# 7_power_prot_mon.net
KiCad netlist of a schematic drawn in Altium Designer
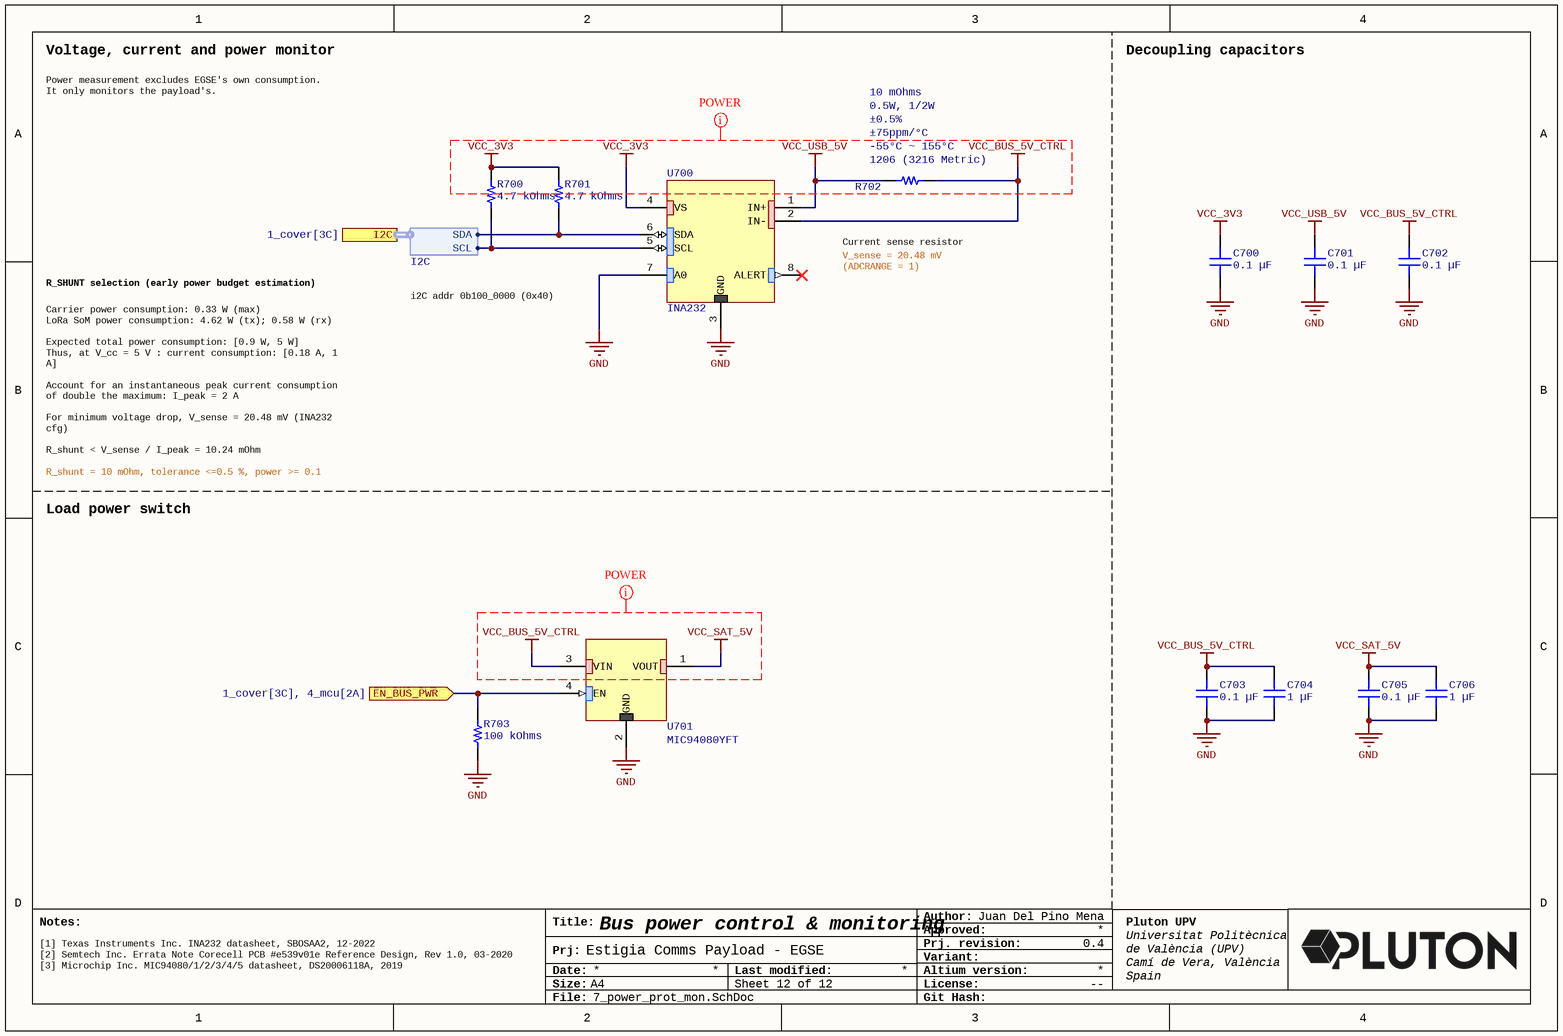
[diagram p0: 7_power_prot_mon.SchDoc]

(export (version "E")
  (design (tool "Eeschema 10.0.6"))
  (components
    (comp (ref "C700")
      (value "0.1 µF")
      (footprint "CAP 0402_1005")
      (description "CAP CER 0402 0.1UF 16V X7R 10%")
      (fields (field (name "PART NUMBER") "C0402C104K4RECAUTO") (field (name "MANUFACTURER") "KEMET"))
      (libsource (lib "Celestial Altium Library - altium_library") (part "Capacitor"))
    )
    (comp (ref "C701")
      (value "0.1 µF")
      (footprint "CAP 0402_1005")
      (description "CAP CER 0402 0.1UF 16V X7R 10%")
      (fields (field (name "PART NUMBER") "C0402C104K4RECAUTO") (field (name "MANUFACTURER") "KEMET"))
      (libsource (lib "Celestial Altium Library - altium_library") (part "Capacitor"))
    )
    (comp (ref "C702")
      (value "0.1 µF")
      (footprint "CAP 0402_1005")
      (description "CAP CER 0402 0.1UF 16V X7R 10%")
      (fields (field (name "PART NUMBER") "C0402C104K4RECAUTO") (field (name "MANUFACTURER") "KEMET"))
      (libsource (lib "Celestial Altium Library - altium_library") (part "Capacitor"))
    )
    (comp (ref "C703")
      (value "0.1 µF")
      (footprint "CAP 0402_1005")
      (description "CAP CER 0402 0.1UF 16V X7R 10%")
      (fields (field (name "PART NUMBER") "C0402C104K4RECAUTO") (field (name "MANUFACTURER") "KEMET"))
      (libsource (lib "Celestial Altium Library - altium_library") (part "Capacitor"))
    )
    (comp (ref "C704")
      (value "1 µF")
      (footprint "CAP 0402_1005")
      (description "CAP CER 1UF 10V X7S 0402")
      (fields
        (field (name "PART NUMBER") "GRT155C71A105KE13D")
        (field (name "MANUFACTURER") "Murata Electronics")
      )
      (libsource (lib "Celestial Altium Library - altium_library") (part "Capacitor"))
    )
    (comp (ref "C705")
      (value "0.1 µF")
      (footprint "CAP 0402_1005")
      (description "CAP CER 0402 0.1UF 16V X7R 10%")
      (fields (field (name "PART NUMBER") "C0402C104K4RECAUTO") (field (name "MANUFACTURER") "KEMET"))
      (libsource (lib "Celestial Altium Library - altium_library") (part "Capacitor"))
    )
    (comp (ref "C706")
      (value "1 µF")
      (footprint "CAP 0402_1005")
      (description "CAP CER 1UF 10V X7S 0402")
      (fields
        (field (name "PART NUMBER") "GRT155C71A105KE13D")
        (field (name "MANUFACTURER") "Murata Electronics")
      )
      (libsource (lib "Celestial Altium Library - altium_library") (part "Capacitor"))
    )
    (comp (ref "R700")
      (value "4.7 kOhms")
      (footprint "RES 0201_0603")
      (description "RES SMD 4.7K OHM 1% 1/20W 0201")
      (fields (field (name "PART NUMBER") "AC0201FR-074K7L") (field (name "MANUFACTURER") "Yageo"))
      (libsource (lib "Celestial Altium Library - altium_library") (part "Resistor"))
    )
    (comp (ref "R701")
      (value "4.7 kOhms")
      (footprint "RES 0201_0603")
      (description "RES SMD 4.7K OHM 1% 1/20W 0201")
      (fields (field (name "PART NUMBER") "AC0201FR-074K7L") (field (name "MANUFACTURER") "Yageo"))
      (libsource (lib "Celestial Altium Library - altium_library") (part "Resistor"))
    )
    (comp (ref "R702")
      (value "10 mOhms")
      (footprint "STACKPOLE CSR1206")
      (description "0.01 OHM 1206 0.5% 0.50W")
      (fields
        (field (name "PART NUMBER") "L4T12FR010DER")
        (field (name "PACKAGE / CASE") "1206 (3216 Metric)")
        (field (name "MANUFACTURER") "Ohmite")
        (field (name "OPERATING TEMPERATURE") "-55°C ~ 155°C")
        (field (name "POWER (WATTS)") "0.5W, 1/2W")
        (field (name "RESISTANCE") "10 mOhms")
        (field (name "TEMPERATURE COEFFICIENT") "±75ppm/°C")
        (field (name "TOLERANCE") "±0.5%")
      )
      (libsource (lib "Celestial Altium Library - altium_library") (part "Resistor"))
    )
    (comp (ref "R703")
      (value "100 kOhms")
      (footprint "RES 0201_0603")
      (description "RES 100K OHM 1% 1/20W 0201")
      (fields (field (name "PART NUMBER") "RC0201FR-13100KL") (field (name "MANUFACTURER") "Yageo"))
      (libsource (lib "Celestial Altium Library - altium_library") (part "Resistor"))
    )
    (comp (ref "U700")
      (value "INA232")
      (footprint "ics:SOp-23-8")
      (description "48-V, 16-Bit, Current, Voltage, and Power Monitor With an I2C Interface")
      (libsource (lib "power") (part "INA232"))
    )
    (comp (ref "U701")
      (value "MIC94080YFT")
      (footprint "ics:MIC94080YFT")
      (description "67 mΩ RDS(ON) 2A High-Side Load Switch in 0.85 mm x 0.85 mm FTDFN Package")
      (libsource (lib "power") (part "MIC94080YFT"))
    )
  )
  (nets
    (net (code "2") (name "/EN_BUS_PWR") (class "Default")
      (node (ref "R703") (pin "1") (pinfunction "1_1") (pintype "passive"))
      (node (ref "U701") (pin "4") (pinfunction "EN_4") (pintype "input"))
    )
    (net (code "4") (name "GND") (class "Default")
      (node (ref "C700") (pin "1") (pinfunction "1_1") (pintype "passive"))
      (node (ref "C701") (pin "1") (pinfunction "1_1") (pintype "passive"))
      (node (ref "C702") (pin "1") (pinfunction "1_1") (pintype "passive"))
      (node (ref "C703") (pin "1") (pinfunction "1_1") (pintype "passive"))
      (node (ref "C704") (pin "1") (pinfunction "1_1") (pintype "passive"))
      (node (ref "C705") (pin "1") (pinfunction "1_1") (pintype "passive"))
      (node (ref "C706") (pin "1") (pinfunction "1_1") (pintype "passive"))
      (node (ref "R703") (pin "2") (pinfunction "2_2") (pintype "passive"))
      (node (ref "U700") (pin "3") (pinfunction "GND_3") (pintype "passive"))
      (node (ref "U700") (pin "7") (pinfunction "A0_7") (pintype "passive"))
      (node (ref "U701") (pin "2") (pinfunction "GND_2") (pintype "power_in"))
    )
    (net (code "5") (name "Net-(U700-SCL)") (class "Default")
      (node (ref "R700") (pin "1") (pinfunction "1_1") (pintype "passive"))
      (node (ref "U700") (pin "5") (pinfunction "SCL_5") (pintype "bidirectional"))
    )
    (net (code "6") (name "Net-(U700-SDA)") (class "Default")
      (node (ref "R701") (pin "1") (pinfunction "1_1") (pintype "passive"))
      (node (ref "U700") (pin "6") (pinfunction "SDA_6") (pintype "bidirectional"))
    )
    (net (code "7") (name "VCC_3V3") (class "Default")
      (node (ref "C700") (pin "2") (pinfunction "2_2") (pintype "passive"))
      (node (ref "R700") (pin "2") (pinfunction "2_2") (pintype "passive"))
      (node (ref "R701") (pin "2") (pinfunction "2_2") (pintype "passive"))
      (node (ref "U700") (pin "4") (pinfunction "VS_4") (pintype "power_in"))
    )
    (net (code "8") (name "VCC_BUS_5V_CTRL") (class "Default")
      (node (ref "C702") (pin "2") (pinfunction "2_2") (pintype "passive"))
      (node (ref "C703") (pin "2") (pinfunction "2_2") (pintype "passive"))
      (node (ref "C704") (pin "2") (pinfunction "2_2") (pintype "passive"))
      (node (ref "R702") (pin "1") (pinfunction "1_1") (pintype "passive"))
      (node (ref "U700") (pin "2") (pinfunction "IN-_2") (pintype "power_in"))
      (node (ref "U701") (pin "3") (pinfunction "VIN_3") (pintype "power_in"))
    )
    (net (code "9") (name "VCC_SAT_5V") (class "Default")
      (node (ref "C705") (pin "2") (pinfunction "2_2") (pintype "passive"))
      (node (ref "C706") (pin "2") (pinfunction "2_2") (pintype "passive"))
      (node (ref "U701") (pin "1") (pinfunction "VOUT_1") (pintype "power_in"))
    )
    (net (code "10") (name "VCC_USB_5V") (class "Default")
      (node (ref "C701") (pin "2") (pinfunction "2_2") (pintype "passive"))
      (node (ref "R702") (pin "2") (pinfunction "2_2") (pintype "passive"))
      (node (ref "U700") (pin "1") (pinfunction "IN+_1") (pintype "power_in"))
    )
    (net (code "11") (name "unconnected-(U700-ALERT-Pad8)") (class "Default")
      (node (ref "U700") (pin "8") (pinfunction "ALERT_8") (pintype "output+no_connect"))
    )
  )
)
